# Levels.net
KiCad netlist of a schematic drawn in Altium Designer
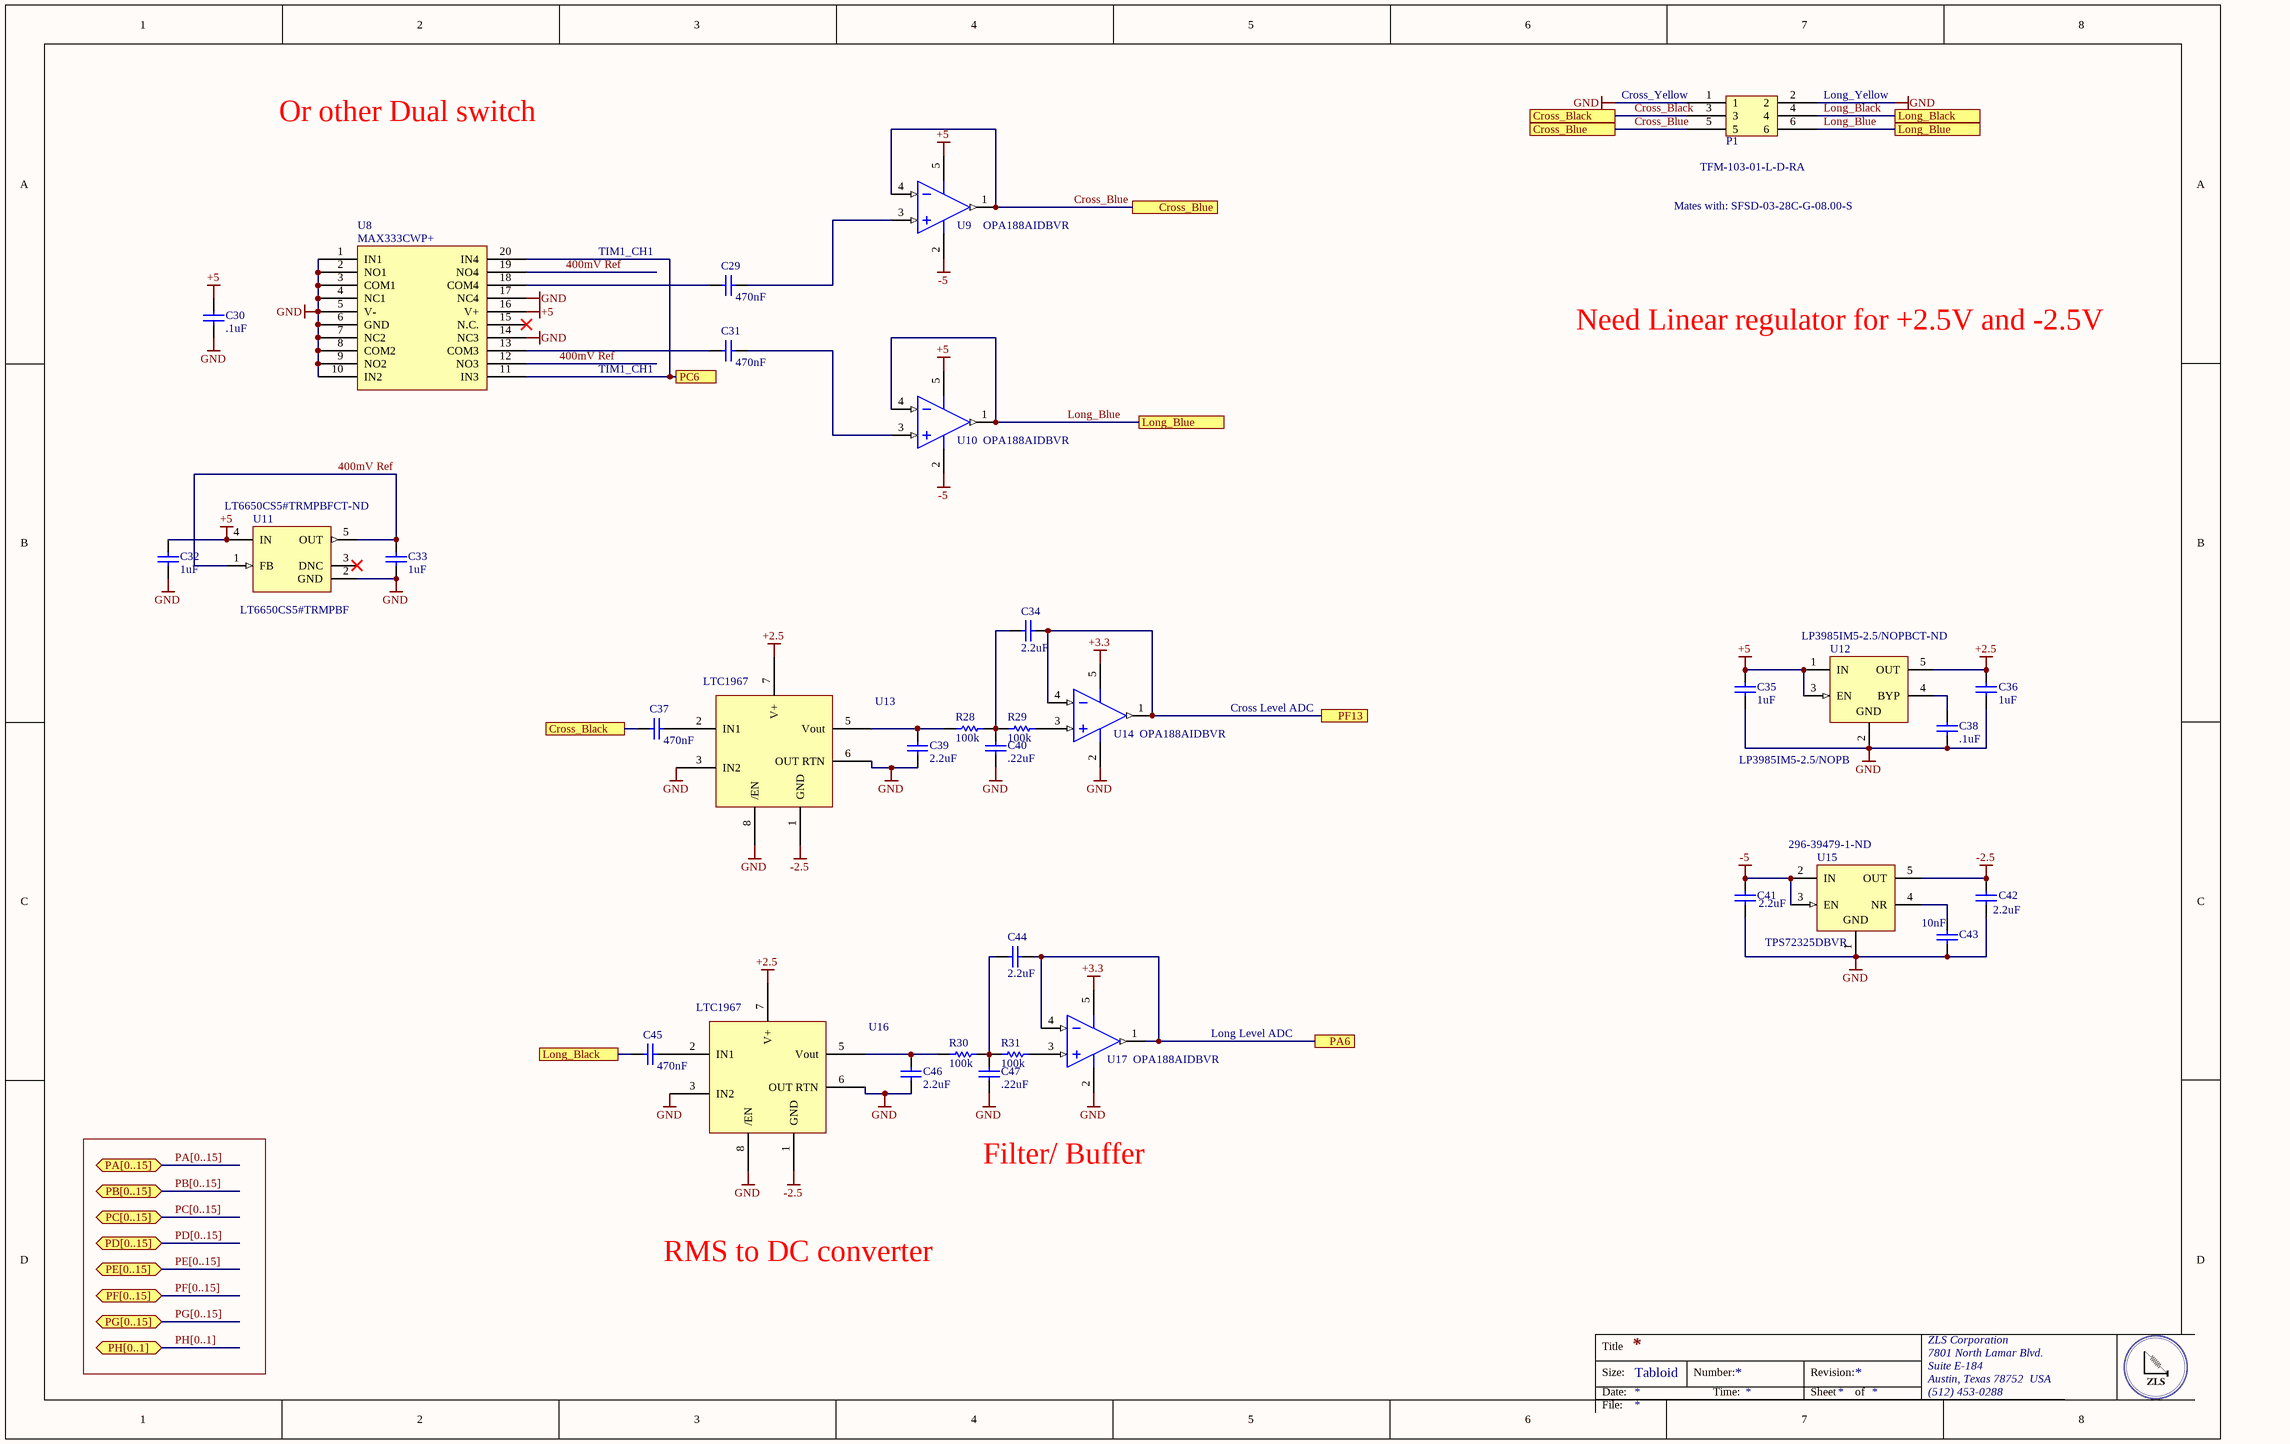
[diagram p0: Levels.SchDoc]

(export (version "E")
  (design (tool "Eeschema 10.0.6"))
  (components
    (comp (ref "C29")
      (value "470nF")
      (footprint "CAPC0805(2012)75_L")
      (description "CAP 150pF 16V ±10% 0805 (2012 Metric) Thickness 0.75mm SMD")
      (fields (field (name "TOLERANCE") "Â±10%"))
      (libsource (lib "Altium Content Vault") (part "CMP-1036-02117-1"))
    )
    (comp (ref "C30")
      (value ".1uF")
      (footprint "CAPC0805(2012)75_L")
      (description "CAP 150pF 16V ±10% 0805 (2012 Metric) Thickness 0.75mm SMD")
      (fields (field (name "TOLERANCE") "Â±10%"))
      (libsource (lib "Altium Content Vault") (part "CMP-1036-02117-1"))
    )
    (comp (ref "C31")
      (value "470nF")
      (footprint "CAPC0805(2012)75_L")
      (description "CAP 150pF 16V ±10% 0805 (2012 Metric) Thickness 0.75mm SMD")
      (fields (field (name "TOLERANCE") "Â±10%"))
      (libsource (lib "Altium Content Vault") (part "CMP-1036-02117-1"))
    )
    (comp (ref "C32")
      (value "08053C105JAT2A")
      (footprint "CAPC0805(2012)145_N")
      (description "1µF ±5% 25V Ceramic Capacitor X7R 0805 (2012 Metric)")
      (fields
        (field (name "TOLERANCE") "Â±5%")
        (field (name "MANUFACTURER") "Kyocera AVX")
        (field (name "CAPACITANCE") "1uF")
      )
      (libsource (lib "Altium Content Vault") (part "CAP"))
    )
    (comp (ref "C33")
      (value "08053C105JAT2A")
      (footprint "CAPC0805(2012)145_N")
      (description "1µF ±5% 25V Ceramic Capacitor X7R 0805 (2012 Metric)")
      (fields
        (field (name "TOLERANCE") "Â±5%")
        (field (name "MANUFACTURER") "Kyocera AVX")
        (field (name "CAPACITANCE") "1uF")
      )
      (libsource (lib "Altium Content Vault") (part "CAP"))
    )
    (comp (ref "C34")
      (value "2.2uF")
      (footprint "CAPC0805(2012)75_L")
      (description "CAP 150pF 16V ±10% 0805 (2012 Metric) Thickness 0.75mm SMD")
      (fields (field (name "TOLERANCE") "Â±10%"))
      (libsource (lib "Altium Content Vault") (part "CMP-1036-02117-1"))
    )
    (comp (ref "C35")
      (value "08053C105JAT2A")
      (footprint "CAPC0805(2012)145_N")
      (description "1µF ±5% 25V Ceramic Capacitor X7R 0805 (2012 Metric)")
      (fields
        (field (name "TOLERANCE") "Â±5%")
        (field (name "MANUFACTURER") "Kyocera AVX")
        (field (name "CAPACITANCE") "1uF")
      )
      (libsource (lib "Altium Content Vault") (part "CAP"))
    )
    (comp (ref "C36")
      (value "08053C105JAT2A")
      (footprint "CAPC0805(2012)145_N")
      (description "1µF ±5% 25V Ceramic Capacitor X7R 0805 (2012 Metric)")
      (fields
        (field (name "TOLERANCE") "Â±5%")
        (field (name "MANUFACTURER") "Kyocera AVX")
        (field (name "CAPACITANCE") "1uF")
      )
      (libsource (lib "Altium Content Vault") (part "CAP"))
    )
    (comp (ref "C37")
      (value "470nF")
      (footprint "CAPC0805(2012)75_L")
      (description "CAP 150pF 16V ±10% 0805 (2012 Metric) Thickness 0.75mm SMD")
      (fields (field (name "TOLERANCE") "Â±10%"))
      (libsource (lib "Altium Content Vault") (part "CMP-1036-02117-1"))
    )
    (comp (ref "C38")
      (value ".1uF")
      (footprint "CAPC0805(2012)75_L")
      (description "0.1µF ±10% 25V Ceramic Capacitor X7R 0805 (2012 Metric)")
      (fields
        (field (name "MANUFACTURER") "Vishay")
        (field (name "MANUFACTURER PART NUMBER") "VJ0805Y104KXXCW1BC")
      )
      (libsource (lib "Altium Content Vault") (part "CMP-1036-02117-1"))
    )
    (comp (ref "C39")
      (value "2.2uF")
      (footprint "CAPC0805(2012)75_L")
      (description "CAP 150pF 16V ±10% 0805 (2012 Metric) Thickness 0.75mm SMD")
      (fields (field (name "TOLERANCE") "Â±10%"))
      (libsource (lib "Altium Content Vault") (part "CMP-1036-02117-1"))
    )
    (comp (ref "C40")
      (value ".22uF")
      (footprint "CAPC0805(2012)75_L")
      (description "CAP 150pF 16V ±10% 0805 (2012 Metric) Thickness 0.75mm SMD")
      (fields (field (name "TOLERANCE") "Â±10%"))
      (libsource (lib "Altium Content Vault") (part "CMP-1036-02117-1"))
    )
    (comp (ref "C41")
      (value "GRM21BR71A225KA01L")
      (footprint "CAPC2013X135X50ML10T20")
      (description "2.2µF ±10% 10V Ceramic Capacitor X7R 0805 (2012 Metric)")
      (fields
        (field (name "MANUFACTURER") "Murata")
        (field (name "CAPACITANCE") "2.2uF")
        (field (name "TOLERANCE") "10%")
      )
      (libsource (lib "Altium Content Vault") (part "CAP"))
    )
    (comp (ref "C42")
      (value "GRM21BR71A225KA01L")
      (footprint "CAPC2013X135X50ML10T20")
      (description "2.2µF ±10% 10V Ceramic Capacitor X7R 0805 (2012 Metric)")
      (fields
        (field (name "MANUFACTURER") "Murata")
        (field (name "CAPACITANCE") "2.2uF")
        (field (name "TOLERANCE") "10%")
      )
      (libsource (lib "Altium Content Vault") (part "CAP"))
    )
    (comp (ref "C43")
      (value "0805ZC103KAT2A")
      (footprint "CAPC2013X140X50NL20T25")
      (description "10000pF ±10% 10V Ceramic Capacitor X7R 0805 (2012 Metric)")
      (fields
        (field (name "MANUFACTURER") "AVX Interconnect / Elco")
        (field (name "CAPACITANCE") "10nF")
        (field (name "TOLERANCE") "10%")
      )
      (libsource (lib "Altium Content Vault") (part "CAP"))
    )
    (comp (ref "C44")
      (value "2.2uF")
      (footprint "CAPC0805(2012)75_L")
      (description "CAP 150pF 16V ±10% 0805 (2012 Metric) Thickness 0.75mm SMD")
      (fields (field (name "TOLERANCE") "Â±10%"))
      (libsource (lib "Altium Content Vault") (part "CMP-1036-02117-1"))
    )
    (comp (ref "C45")
      (value "470nF")
      (footprint "CAPC0805(2012)75_L")
      (description "CAP 150pF 16V ±10% 0805 (2012 Metric) Thickness 0.75mm SMD")
      (fields (field (name "TOLERANCE") "Â±10%"))
      (libsource (lib "Altium Content Vault") (part "CMP-1036-02117-1"))
    )
    (comp (ref "C46")
      (value "2.2uF")
      (footprint "CAPC0805(2012)75_L")
      (description "CAP 150pF 16V ±10% 0805 (2012 Metric) Thickness 0.75mm SMD")
      (fields (field (name "TOLERANCE") "Â±10%"))
      (libsource (lib "Altium Content Vault") (part "CMP-1036-02117-1"))
    )
    (comp (ref "C47")
      (value ".22uF")
      (footprint "CAPC0805(2012)75_L")
      (description "CAP 150pF 16V ±10% 0805 (2012 Metric) Thickness 0.75mm SMD")
      (fields (field (name "TOLERANCE") "Â±10%"))
      (libsource (lib "Altium Content Vault") (part "CMP-1036-02117-1"))
    )
    (comp (ref "P1")
      (value "TFM-103-01-L-D-RA")
      (footprint "TFM-103-01-L-D-RA")
      (fields (field (name "MANUFACTURER") "Samtec"))
      (libsource (lib "ZLS_Schematic_lib") (part "TFM-103-01-L-D-RA"))
    )
    (comp (ref "R28")
      (value "100k")
      (footprint "RESC0805(2012)_L")
      (description "2R55 0.125W 1% 0805 (2012 Metric)  SMD")
      (fields (field (name "TOLERANCE") "1 %") (field (name "POWER") "0.125 W"))
      (libsource (lib "Altium Content Vault") (part "CMP-1013-00215-1"))
    )
    (comp (ref "R29")
      (value "100k")
      (footprint "RESC0805(2012)_L")
      (description "2R55 0.125W 1% 0805 (2012 Metric)  SMD")
      (fields (field (name "TOLERANCE") "1 %") (field (name "POWER") "0.125 W"))
      (libsource (lib "Altium Content Vault") (part "CMP-1013-00215-1"))
    )
    (comp (ref "R30")
      (value "100k")
      (footprint "RESC0805(2012)_L")
      (description "2R55 0.125W 1% 0805 (2012 Metric)  SMD")
      (fields (field (name "TOLERANCE") "1 %") (field (name "POWER") "0.125 W"))
      (libsource (lib "Altium Content Vault") (part "CMP-1013-00215-1"))
    )
    (comp (ref "R31")
      (value "100k")
      (footprint "RESC0805(2012)_L")
      (description "2R55 0.125W 1% 0805 (2012 Metric)  SMD")
      (fields (field (name "TOLERANCE") "1 %") (field (name "POWER") "0.125 W"))
      (libsource (lib "Altium Content Vault") (part "CMP-1013-00215-1"))
    )
    (comp (ref "U8")
      (value "MAX333CWP+")
      (footprint "TSOP65P640X90-20N")
      (description "IC SWITCH QUAD SPDT 20TSSOP")
      (fields (field (name "MANUFACTURER") "Maxim") (field (name "MANUFACTURER PART NUMBER") "MAX333AEUP+"))
      (libsource (lib "ZLS_Schematic_lib") (part "MAX333CWP+"))
    )
    (comp (ref "U9")
      (value "OPA188AIDBVR")
      (footprint "DBV0005A_M")
      (fields (field (name "MANUFACTURER") "Texas Instruments"))
      (libsource (lib "Altium Content Vault") (part "CMP-0809-00005-2"))
    )
    (comp (ref "U10")
      (value "OPA188AIDBVR")
      (footprint "DBV0005A_M")
      (fields (field (name "MANUFACTURER") "Texas Instruments"))
      (libsource (lib "Altium Content Vault") (part "CMP-0809-00005-2"))
    )
    (comp (ref "U11")
      (value "LT6650CS5#TRMPBF")
      (footprint "LT-S5-5-TSOT-23_N")
      (fields
        (field (name "SUPPLIER PART NUMBER 1") "LT6650CS5#TRMPBFCT-ND")
        (field (name "MANUFACTURER") "Analog Devices / Linear Technology")
        (field (name "TOLERANCE") "0.75%")
      )
      (libsource (lib "Altium Content Vault") (part "LT-LT6650-S5-5"))
    )
    (comp (ref "U12")
      (value "LP3985IM5-2.5/NOPB")
      (footprint "DBV0005A_M")
      (description "Micropower, 150mA Low-Noise Ultra Low-Dropout CMOS Voltage Regulator, 5-pin SOT-23, Pb-Free")
      (fields
        (field (name "MANUFACTURER") "Texas Instruments")
        (field (name "SUPPLIER PART NUMBER 1") "LP3985IM5-2.5/NOPBCT-ND")
      )
      (libsource (lib "Altium Content Vault") (part "PM-REG-LP3985-SOT5"))
    )
    (comp (ref "U13")
      (value "LTC1967")
      (footprint "LTC1967")
      (description "IC CONVERTER RMS-DC PREC 9MSOP")
      (libsource (lib "ZLS_Schematic_lib") (part "LTC1967"))
    )
    (comp (ref "U14")
      (value "OPA188AIDBVR")
      (footprint "DBV0005A_M")
      (fields (field (name "MANUFACTURER") "Texas Instruments"))
      (libsource (lib "Altium Content Vault") (part "CMP-0809-00005-2"))
    )
    (comp (ref "U15")
      (value "TPS72325DBVR")
      (footprint "DBV0005A_N")
      (fields
        (field (name "MANUFACTURER") "Texas Instruments")
        (field (name "SUPPLIER PART NUMBER 1") "296-39479-1-ND")
      )
      (libsource (lib "Altium Content Vault") (part "TI-TPS72325-DBV5"))
    )
    (comp (ref "U16")
      (value "LTC1967")
      (footprint "LTC1967")
      (description "IC CONVERTER RMS-DC PREC 9MSOP")
      (libsource (lib "ZLS_Schematic_lib") (part "LTC1967"))
    )
    (comp (ref "U17")
      (value "OPA188AIDBVR")
      (footprint "DBV0005A_M")
      (fields (field (name "MANUFACTURER") "Texas Instruments"))
      (libsource (lib "Altium Content Vault") (part "CMP-0809-00005-2"))
    )
  )
  (nets
    (net (code "112") (name "+2.5") (class "Default")
      (node (ref "C36") (pin "2") (pinfunction "2_2") (pintype "passive"))
      (node (ref "U12") (pin "5") (pinfunction "OUT_5") (pintype "power_in"))
      (node (ref "U13") (pin "7") (pinfunction "V+_7") (pintype "passive"))
      (node (ref "U16") (pin "7") (pinfunction "V+_7") (pintype "passive"))
    )
    (net (code "113") (name "+3.3") (class "Default")
      (node (ref "U14") (pin "5") (pinfunction "V+_5") (pintype "power_in"))
      (node (ref "U17") (pin "5") (pinfunction "V+_5") (pintype "power_in"))
    )
    (net (code "114") (name "+5") (class "Default")
      (node (ref "C30") (pin "2") (pinfunction "2_2") (pintype "passive"))
      (node (ref "C32") (pin "2") (pinfunction "2_2") (pintype "passive"))
      (node (ref "C35") (pin "2") (pinfunction "2_2") (pintype "passive"))
      (node (ref "U10") (pin "5") (pinfunction "V+_5") (pintype "power_in"))
      (node (ref "U11") (pin "4") (pinfunction "IN_4") (pintype "power_in"))
      (node (ref "U12") (pin "1") (pinfunction "IN_1") (pintype "power_in"))
      (node (ref "U12") (pin "3") (pinfunction "EN_3") (pintype "input"))
      (node (ref "U8") (pin "16") (pinfunction "V+_16") (pintype "power_in"))
      (node (ref "U9") (pin "5") (pinfunction "V+_5") (pintype "power_in"))
    )
    (net (code "115") (name "-2.5") (class "Default")
      (node (ref "C42") (pin "2") (pinfunction "2_2") (pintype "passive"))
      (node (ref "U13") (pin "1") (pinfunction "GND_1") (pintype "passive"))
      (node (ref "U15") (pin "5") (pinfunction "OUT_5") (pintype "power_in"))
      (node (ref "U16") (pin "1") (pinfunction "GND_1") (pintype "passive"))
    )
    (net (code "116") (name "-5") (class "Default")
      (node (ref "C41") (pin "2") (pinfunction "2_2") (pintype "passive"))
      (node (ref "U10") (pin "2") (pinfunction "V-_2") (pintype "power_in"))
      (node (ref "U15") (pin "2") (pinfunction "IN_2") (pintype "power_in"))
      (node (ref "U15") (pin "3") (pinfunction "EN_3") (pintype "input"))
      (node (ref "U9") (pin "2") (pinfunction "V-_2") (pintype "power_in"))
    )
    (net (code "117") (name "/400mV Ref") (class "Default")
      (node (ref "C33") (pin "2") (pinfunction "2_2") (pintype "passive"))
      (node (ref "U11") (pin "1") (pinfunction "FB_1") (pintype "input"))
      (node (ref "U11") (pin "5") (pinfunction "OUT_5") (pintype "output"))
      (node (ref "U8") (pin "12") (pinfunction "NO3_12") (pintype "passive"))
      (node (ref "U8") (pin "19") (pinfunction "NO4_19") (pintype "passive"))
    )
    (net (code "118") (name "/Cross_Black") (class "Default")
      (node (ref "C37") (pin "1") (pinfunction "1_1") (pintype "passive"))
      (node (ref "P1") (pin "3") (pinfunction "3_3") (pintype "passive"))
    )
    (net (code "119") (name "/Cross_Blue") (class "Default")
      (node (ref "P1") (pin "5") (pinfunction "5_5") (pintype "passive"))
      (node (ref "U9") (pin "1") (pinfunction "OUT_1") (pintype "output"))
      (node (ref "U9") (pin "4") (pinfunction "IN-_4") (pintype "input"))
    )
    (net (code "120") (name "/Long_Black") (class "Default")
      (node (ref "C45") (pin "1") (pinfunction "1_1") (pintype "passive"))
      (node (ref "P1") (pin "4") (pinfunction "4_4") (pintype "passive"))
    )
    (net (code "121") (name "/Long_Blue") (class "Default")
      (node (ref "P1") (pin "6") (pinfunction "6_6") (pintype "passive"))
      (node (ref "U10") (pin "1") (pinfunction "OUT_1") (pintype "output"))
      (node (ref "U10") (pin "4") (pinfunction "IN-_4") (pintype "input"))
    )
    (net (code "122") (name "/PA6") (class "Default")
      (node (ref "C44") (pin "1") (pinfunction "1_1") (pintype "passive"))
      (node (ref "U17") (pin "1") (pinfunction "OUT_1") (pintype "output"))
      (node (ref "U17") (pin "4") (pinfunction "IN-_4") (pintype "input"))
    )
    (net (code "125") (name "/PC6") (class "Default")
      (node (ref "U8") (pin "11") (pinfunction "IN3_11") (pintype "passive"))
      (node (ref "U8") (pin "20") (pinfunction "IN4_20") (pintype "passive"))
    )
    (net (code "129") (name "/PF13") (class "Default")
      (node (ref "C34") (pin "1") (pinfunction "1_1") (pintype "passive"))
      (node (ref "U14") (pin "1") (pinfunction "OUT_1") (pintype "output"))
      (node (ref "U14") (pin "4") (pinfunction "IN-_4") (pintype "input"))
    )
    (net (code "133") (name "GND") (class "Default")
      (node (ref "C30") (pin "1") (pinfunction "1_1") (pintype "passive"))
      (node (ref "C32") (pin "1") (pinfunction "1_1") (pintype "passive"))
      (node (ref "C33") (pin "1") (pinfunction "1_1") (pintype "passive"))
      (node (ref "C35") (pin "1") (pinfunction "1_1") (pintype "passive"))
      (node (ref "C36") (pin "1") (pinfunction "1_1") (pintype "passive"))
      (node (ref "C38") (pin "1") (pinfunction "1_1") (pintype "passive"))
      (node (ref "C39") (pin "1") (pinfunction "1_1") (pintype "passive"))
      (node (ref "C40") (pin "1") (pinfunction "1_1") (pintype "passive"))
      (node (ref "C41") (pin "1") (pinfunction "1_1") (pintype "passive"))
      (node (ref "C42") (pin "1") (pinfunction "1_1") (pintype "passive"))
      (node (ref "C43") (pin "1") (pinfunction "1_1") (pintype "passive"))
      (node (ref "C46") (pin "1") (pinfunction "1_1") (pintype "passive"))
      (node (ref "C47") (pin "1") (pinfunction "1_1") (pintype "passive"))
      (node (ref "P1") (pin "1") (pinfunction "1_1") (pintype "passive"))
      (node (ref "P1") (pin "2") (pinfunction "2_2") (pintype "passive"))
      (node (ref "U11") (pin "2") (pinfunction "GND_2") (pintype "power_in"))
      (node (ref "U12") (pin "2") (pinfunction "GND_2") (pintype "power_in"))
      (node (ref "U13") (pin "3") (pinfunction "IN2_3") (pintype "passive"))
      (node (ref "U13") (pin "6") (pinfunction "OUT_RTN_6") (pintype "passive"))
      (node (ref "U13") (pin "8") (pinfunction "/EN_8") (pintype "passive"))
      (node (ref "U14") (pin "2") (pinfunction "V-_2") (pintype "power_in"))
      (node (ref "U15") (pin "1") (pinfunction "GND_1") (pintype "power_in"))
      (node (ref "U16") (pin "3") (pinfunction "IN2_3") (pintype "passive"))
      (node (ref "U16") (pin "6") (pinfunction "OUT_RTN_6") (pintype "passive"))
      (node (ref "U16") (pin "8") (pinfunction "/EN_8") (pintype "passive"))
      (node (ref "U17") (pin "2") (pinfunction "V-_2") (pintype "power_in"))
      (node (ref "U8") (pin "1") (pinfunction "IN1_1") (pintype "passive"))
      (node (ref "U8") (pin "10") (pinfunction "IN2_10") (pintype "passive"))
      (node (ref "U8") (pin "14") (pinfunction "NC3_14") (pintype "passive"))
      (node (ref "U8") (pin "17") (pinfunction "NC4_17") (pintype "passive"))
      (node (ref "U8") (pin "2") (pinfunction "NO1_2") (pintype "passive"))
      (node (ref "U8") (pin "3") (pinfunction "COM1_3") (pintype "passive"))
      (node (ref "U8") (pin "4") (pinfunction "NC1_4") (pintype "passive"))
      (node (ref "U8") (pin "5") (pinfunction "V-_5") (pintype "power_in"))
      (node (ref "U8") (pin "6") (pinfunction "GND_6") (pintype "passive"))
      (node (ref "U8") (pin "7") (pinfunction "NC2_7") (pintype "passive"))
      (node (ref "U8") (pin "8") (pinfunction "COM2_8") (pintype "passive"))
      (node (ref "U8") (pin "9") (pinfunction "NO2_9") (pintype "passive"))
    )
    (net (code "134") (name "Net-(C34-Pad2)") (class "Default")
      (node (ref "C34") (pin "2") (pinfunction "2_2") (pintype "passive"))
      (node (ref "C40") (pin "2") (pinfunction "2_2") (pintype "passive"))
      (node (ref "R28") (pin "1") (pinfunction "1_1") (pintype "passive"))
      (node (ref "R29") (pin "2") (pinfunction "2_2") (pintype "passive"))
    )
    (net (code "135") (name "Net-(C44-Pad2)") (class "Default")
      (node (ref "C44") (pin "2") (pinfunction "2_2") (pintype "passive"))
      (node (ref "C47") (pin "2") (pinfunction "2_2") (pintype "passive"))
      (node (ref "R30") (pin "1") (pinfunction "1_1") (pintype "passive"))
      (node (ref "R31") (pin "2") (pinfunction "2_2") (pintype "passive"))
    )
    (net (code "136") (name "Net-(U8-COM3)") (class "Default")
      (node (ref "C31") (pin "1") (pinfunction "1_1") (pintype "passive"))
      (node (ref "U8") (pin "13") (pinfunction "COM3_13") (pintype "passive"))
    )
    (net (code "137") (name "Net-(U8-COM4)") (class "Default")
      (node (ref "C29") (pin "1") (pinfunction "1_1") (pintype "passive"))
      (node (ref "U8") (pin "18") (pinfunction "COM4_18") (pintype "passive"))
    )
    (net (code "138") (name "Net-(U9-IN+)") (class "Default")
      (node (ref "C29") (pin "2") (pinfunction "2_2") (pintype "passive"))
      (node (ref "U9") (pin "3") (pinfunction "IN+_3") (pintype "input"))
    )
    (net (code "139") (name "Net-(U10-IN+)") (class "Default")
      (node (ref "C31") (pin "2") (pinfunction "2_2") (pintype "passive"))
      (node (ref "U10") (pin "3") (pinfunction "IN+_3") (pintype "input"))
    )
    (net (code "140") (name "Net-(U12-BYP)") (class "Default")
      (node (ref "C38") (pin "2") (pinfunction "2_2") (pintype "passive"))
      (node (ref "U12") (pin "4") (pinfunction "BYP_4") (pintype "passive"))
    )
    (net (code "141") (name "Net-(U13-IN1)") (class "Default")
      (node (ref "C37") (pin "2") (pinfunction "2_2") (pintype "passive"))
      (node (ref "U13") (pin "2") (pinfunction "IN1_2") (pintype "passive"))
    )
    (net (code "142") (name "Net-(U13-Vout)") (class "Default")
      (node (ref "C39") (pin "2") (pinfunction "2_2") (pintype "passive"))
      (node (ref "R28") (pin "2") (pinfunction "2_2") (pintype "passive"))
      (node (ref "U13") (pin "5") (pinfunction "Vout_5") (pintype "passive"))
    )
    (net (code "143") (name "Net-(U14-IN+)") (class "Default")
      (node (ref "R29") (pin "1") (pinfunction "1_1") (pintype "passive"))
      (node (ref "U14") (pin "3") (pinfunction "IN+_3") (pintype "input"))
    )
    (net (code "144") (name "Net-(U15-NR)") (class "Default")
      (node (ref "C43") (pin "2") (pinfunction "2_2") (pintype "passive"))
      (node (ref "U15") (pin "4") (pinfunction "NR_4") (pintype "passive"))
    )
    (net (code "145") (name "Net-(U16-IN1)") (class "Default")
      (node (ref "C45") (pin "2") (pinfunction "2_2") (pintype "passive"))
      (node (ref "U16") (pin "2") (pinfunction "IN1_2") (pintype "passive"))
    )
    (net (code "146") (name "Net-(U16-Vout)") (class "Default")
      (node (ref "C46") (pin "2") (pinfunction "2_2") (pintype "passive"))
      (node (ref "R30") (pin "2") (pinfunction "2_2") (pintype "passive"))
      (node (ref "U16") (pin "5") (pinfunction "Vout_5") (pintype "passive"))
    )
    (net (code "147") (name "Net-(U17-IN+)") (class "Default")
      (node (ref "R31") (pin "1") (pinfunction "1_1") (pintype "passive"))
      (node (ref "U17") (pin "3") (pinfunction "IN+_3") (pintype "input"))
    )
    (net (code "148") (name "unconnected-(U8-N.C.-Pad15)") (class "Default")
      (node (ref "U8") (pin "15") (pinfunction "N.C._15") (pintype "passive+no_connect"))
    )
    (net (code "149") (name "unconnected-(U11-DNC-Pad3)") (class "Default")
      (node (ref "U11") (pin "3") (pinfunction "DNC_3") (pintype "passive+no_connect"))
    )
    (net (code "150") (name "unconnected-(U13-NC-Pad4)") (class "Default")
      (node (ref "U13") (pin "4") (pinfunction "NC_4") (pintype "passive"))
    )
    (net (code "151") (name "unconnected-(U16-NC-Pad4)") (class "Default")
      (node (ref "U16") (pin "4") (pinfunction "NC_4") (pintype "passive"))
    )
  )
)
